# 02_HDMI.net
KiCad netlist of a schematic drawn in Altium Designer
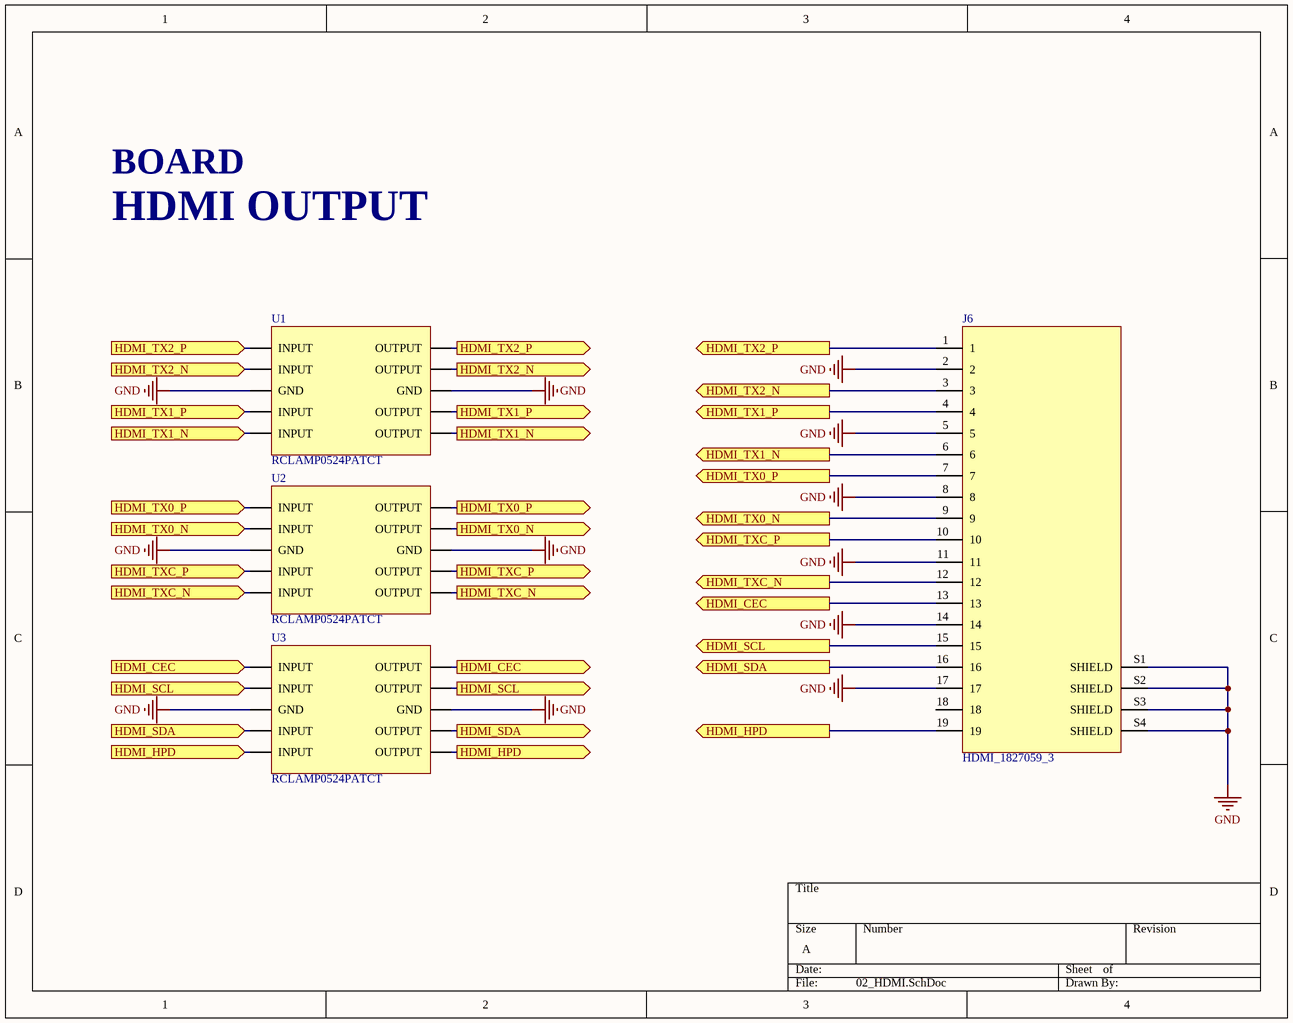
[diagram p0: 02_HDMI.SchDoc]

(export (version "E")
  (design (tool "Eeschema 10.0.6"))
  (components
    (comp (ref "J6")
      (value "HDMI_1827059_3")
      (footprint "HDMI_1827059_3")
      (libsource (lib "MotherBoard") (part "HDMI_1827059_3"))
    )
    (comp (ref "U1")
      (value "RCLAMP0524PATCT")
      (footprint "RCLAMP0524PATCT")
      (libsource (lib "MotherBoard") (part "RCLAMP0524PATCT"))
    )
    (comp (ref "U2")
      (value "RCLAMP0524PATCT")
      (footprint "RCLAMP0524PATCT")
      (libsource (lib "MotherBoard") (part "RCLAMP0524PATCT"))
    )
    (comp (ref "U3")
      (value "RCLAMP0524PATCT")
      (footprint "RCLAMP0524PATCT")
      (libsource (lib "MotherBoard") (part "RCLAMP0524PATCT"))
    )
  )
  (nets
    (net (code "1") (name "/HDMI_CEC") (class "Default")
      (node (ref "J6") (pin "13") (pinfunction "13_13") (pintype "passive"))
      (node (ref "U3") (pin "1") (pinfunction "INPUT_1") (pintype "passive"))
      (node (ref "U3") (pin "10") (pinfunction "OUTPUT_10") (pintype "passive"))
    )
    (net (code "2") (name "/HDMI_HPD") (class "Default")
      (node (ref "J6") (pin "19") (pinfunction "19_19") (pintype "passive"))
      (node (ref "U3") (pin "5") (pinfunction "INPUT_5") (pintype "passive"))
      (node (ref "U3") (pin "6") (pinfunction "OUTPUT_6") (pintype "passive"))
    )
    (net (code "3") (name "/HDMI_SCL") (class "Default")
      (node (ref "J6") (pin "15") (pinfunction "15_15") (pintype "passive"))
      (node (ref "U3") (pin "2") (pinfunction "INPUT_2") (pintype "passive"))
      (node (ref "U3") (pin "9") (pinfunction "OUTPUT_9") (pintype "passive"))
    )
    (net (code "4") (name "/HDMI_SDA") (class "Default")
      (node (ref "J6") (pin "16") (pinfunction "16_16") (pintype "passive"))
      (node (ref "U3") (pin "4") (pinfunction "INPUT_4") (pintype "passive"))
      (node (ref "U3") (pin "7") (pinfunction "OUTPUT_7") (pintype "passive"))
    )
    (net (code "5") (name "/HDMI_TX0_N") (class "Default")
      (node (ref "J6") (pin "9") (pinfunction "9_9") (pintype "passive"))
      (node (ref "U2") (pin "2") (pinfunction "INPUT_2") (pintype "passive"))
      (node (ref "U2") (pin "9") (pinfunction "OUTPUT_9") (pintype "passive"))
    )
    (net (code "6") (name "/HDMI_TX0_P") (class "Default")
      (node (ref "J6") (pin "7") (pinfunction "7_7") (pintype "passive"))
      (node (ref "U2") (pin "1") (pinfunction "INPUT_1") (pintype "passive"))
      (node (ref "U2") (pin "10") (pinfunction "OUTPUT_10") (pintype "passive"))
    )
    (net (code "7") (name "/HDMI_TX1_N") (class "Default")
      (node (ref "J6") (pin "6") (pinfunction "6_6") (pintype "passive"))
      (node (ref "U1") (pin "5") (pinfunction "INPUT_5") (pintype "passive"))
      (node (ref "U1") (pin "6") (pinfunction "OUTPUT_6") (pintype "passive"))
    )
    (net (code "8") (name "/HDMI_TX1_P") (class "Default")
      (node (ref "J6") (pin "4") (pinfunction "4_4") (pintype "passive"))
      (node (ref "U1") (pin "4") (pinfunction "INPUT_4") (pintype "passive"))
      (node (ref "U1") (pin "7") (pinfunction "OUTPUT_7") (pintype "passive"))
    )
    (net (code "9") (name "/HDMI_TX2_N") (class "Default")
      (node (ref "J6") (pin "3") (pinfunction "3_3") (pintype "passive"))
      (node (ref "U1") (pin "2") (pinfunction "INPUT_2") (pintype "passive"))
      (node (ref "U1") (pin "9") (pinfunction "OUTPUT_9") (pintype "passive"))
    )
    (net (code "10") (name "/HDMI_TX2_P") (class "Default")
      (node (ref "J6") (pin "1") (pinfunction "1_1") (pintype "passive"))
      (node (ref "U1") (pin "1") (pinfunction "INPUT_1") (pintype "passive"))
      (node (ref "U1") (pin "10") (pinfunction "OUTPUT_10") (pintype "passive"))
    )
    (net (code "11") (name "/HDMI_TXC_N") (class "Default")
      (node (ref "J6") (pin "12") (pinfunction "12_12") (pintype "passive"))
      (node (ref "U2") (pin "5") (pinfunction "INPUT_5") (pintype "passive"))
      (node (ref "U2") (pin "6") (pinfunction "OUTPUT_6") (pintype "passive"))
    )
    (net (code "12") (name "/HDMI_TXC_P") (class "Default")
      (node (ref "J6") (pin "10") (pinfunction "10_10") (pintype "passive"))
      (node (ref "U2") (pin "4") (pinfunction "INPUT_4") (pintype "passive"))
      (node (ref "U2") (pin "7") (pinfunction "OUTPUT_7") (pintype "passive"))
    )
    (net (code "13") (name "GND") (class "Default")
      (node (ref "J6") (pin "11") (pinfunction "11_11") (pintype "passive"))
      (node (ref "J6") (pin "14") (pinfunction "14_14") (pintype "passive"))
      (node (ref "J6") (pin "17") (pinfunction "17_17") (pintype "passive"))
      (node (ref "J6") (pin "2") (pinfunction "2_2") (pintype "passive"))
      (node (ref "J6") (pin "5") (pinfunction "5_5") (pintype "passive"))
      (node (ref "J6") (pin "8") (pinfunction "8_8") (pintype "passive"))
      (node (ref "J6") (pin "S1") (pinfunction "SHIELD_S1") (pintype "passive"))
      (node (ref "J6") (pin "S2") (pinfunction "SHIELD_S2") (pintype "passive"))
      (node (ref "J6") (pin "S3") (pinfunction "SHIELD_S3") (pintype "passive"))
      (node (ref "J6") (pin "S4") (pinfunction "SHIELD_S4") (pintype "passive"))
      (node (ref "U1") (pin "3") (pinfunction "GND_3") (pintype "passive"))
      (node (ref "U1") (pin "8") (pinfunction "GND_8") (pintype "passive"))
      (node (ref "U2") (pin "3") (pinfunction "GND_3") (pintype "passive"))
      (node (ref "U2") (pin "8") (pinfunction "GND_8") (pintype "passive"))
      (node (ref "U3") (pin "3") (pinfunction "GND_3") (pintype "passive"))
      (node (ref "U3") (pin "8") (pinfunction "GND_8") (pintype "passive"))
    )
    (net (code "14") (name "unconnected-(J6-Pad18)") (class "Default")
      (node (ref "J6") (pin "18") (pinfunction "18_18") (pintype "passive"))
    )
  )
)
